# Mainboard.net
KiCad netlist of a schematic drawn in Altium Designer
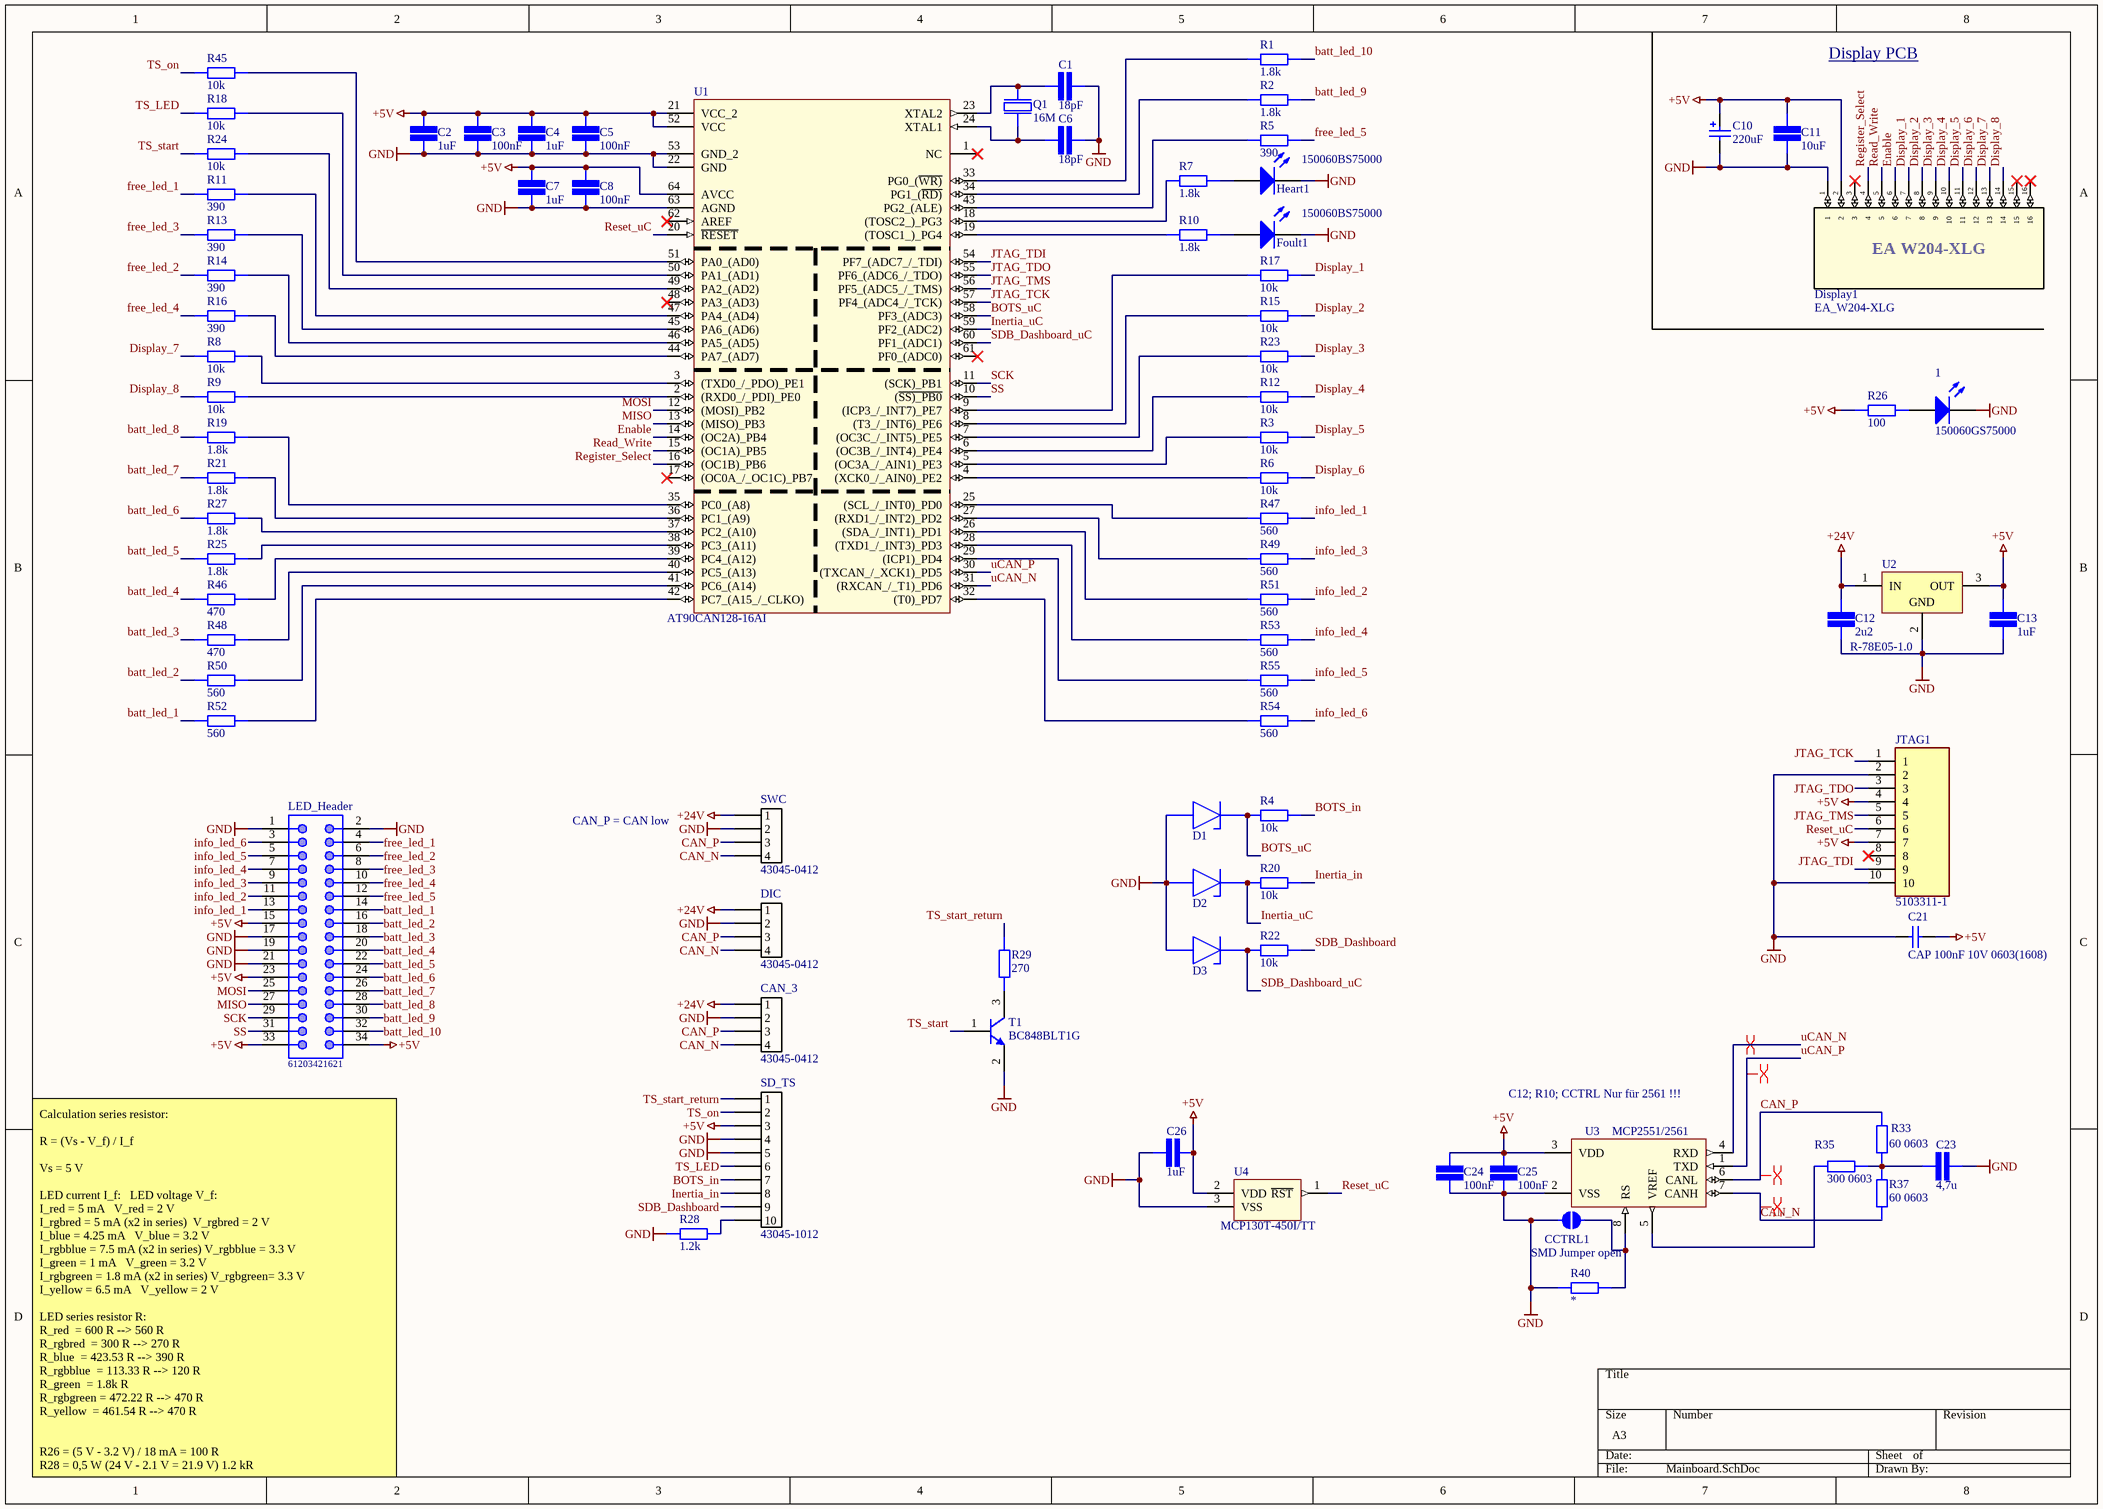
[diagram p0: Mainboard.SchDoc]

(export (version "E")
  (design (tool "Eeschema 10.0.6"))
  (components
    (comp (ref "1")
      (value "150060GS75000")
      (footprint "0603_A")
      (description "SMD mono-color Chip LED, WL-SMCW, Green")
      (fields (field (name "MANUFACTURER") "Wuerth Elektronik"))
      (libsource (lib "Altium Content Vault") (part "WE-LED_K1A2-2"))
    )
    (comp (ref "C1")
      (value "18pF")
      (footprint "CAP 0603/1608")
      (description "Capacitor with multiple Footprints")
      (fields (field (name "Comment") "SMD Capacitor"))
      (libsource (lib "Standardbauteile") (part "SMD Capacitor"))
    )
    (comp (ref "C2")
      (value "1uF")
      (footprint "CAP 0603/1608")
      (description "Capacitor with multiple Footprints")
      (fields (field (name "Comment") "SMD Capacitor"))
      (libsource (lib "") (part "SMD Capacitor_1"))
    )
    (comp (ref "C3")
      (value "100nF")
      (footprint "CAP 0603/1608")
      (description "Capacitor with multiple Footprints")
      (fields (field (name "Comment") "SMD Capacitor"))
      (libsource (lib "") (part "SMD Capacitor_1"))
    )
    (comp (ref "C4")
      (value "1uF")
      (footprint "CAP 0603/1608")
      (description "Capacitor with multiple Footprints")
      (fields (field (name "Comment") "SMD Capacitor"))
      (libsource (lib "") (part "SMD Capacitor_1"))
    )
    (comp (ref "C5")
      (value "100nF")
      (footprint "CAP 0603/1608")
      (description "Capacitor with multiple Footprints")
      (fields (field (name "Comment") "SMD Capacitor"))
      (libsource (lib "") (part "SMD Capacitor_1"))
    )
    (comp (ref "C6")
      (value "18pF")
      (footprint "CAP 0603/1608")
      (description "Capacitor with multiple Footprints")
      (fields (field (name "Comment") "SMD Capacitor"))
      (libsource (lib "Standardbauteile") (part "SMD Capacitor"))
    )
    (comp (ref "C7")
      (value "1uF")
      (footprint "CAP 0603/1608")
      (description "Capacitor with multiple Footprints")
      (fields (field (name "Comment") "SMD Capacitor"))
      (libsource (lib "") (part "SMD Capacitor_1"))
    )
    (comp (ref "C8")
      (value "100nF")
      (footprint "CAP 0603/1608")
      (description "Capacitor with multiple Footprints")
      (fields (field (name "Comment") "SMD Capacitor"))
      (libsource (lib "") (part "SMD Capacitor_1"))
    )
    (comp (ref "C10")
      (value "220uF")
      (footprint "WCAP-ASLL_6.3x7.7")
      (description "WCAP-ASLL Aluminum Electrolytic Capacitors, size Ф6.3x7.7mm, 6.3V DC, 220uF")
      (fields (field (name "PART NUMBER") "865060145006") (field (name "PUBLISHER") "Wurth Elektronik"))
      (libsource (lib "ALTIUM-WCAP-ASLL-rev17a") (part "865060145006"))
    )
    (comp (ref "C11")
      (value "10uF")
      (footprint "CAP 0603/1608")
      (description "Capacitor with multiple Footprints")
      (fields (field (name "Comment") "SMD Capacitor"))
      (libsource (lib "") (part "SMD Capacitor_2"))
    )
    (comp (ref "C12")
      (value "2u2")
      (footprint "CAP 0603/1608")
      (description "Capacitor with multiple Footprints")
      (fields (field (name "Comment") "SMD Capacitor"))
      (libsource (lib "") (part "SMD Capacitor_1"))
    )
    (comp (ref "C13")
      (value "1uF")
      (footprint "CAP 0603/1608")
      (description "Capacitor with multiple Footprints")
      (fields (field (name "Comment") "SMD Capacitor"))
      (libsource (lib "") (part "SMD Capacitor_1"))
    )
    (comp (ref "C21")
      (value "CAP 100nF 10V 0603(1608)")
      (footprint "CAPC0603(1608)100_L")
      (description "CAP 100nF 10V ±5% 0603 (1608 Metric) Thickness 1mm SMD")
      (fields (field (name "TOLERANCE") "Â±5%"))
      (libsource (lib "Altium Content Vault") (part "CAP"))
    )
    (comp (ref "C23")
      (value "4,7u")
      (footprint "CAP 0603/1608")
      (description "Capacitor with multiple Footprints")
      (fields (field (name "Comment") "SMD Capacitor"))
      (libsource (lib "") (part "SMD Capacitor_3"))
    )
    (comp (ref "C24")
      (value "100nF")
      (footprint "CAP 0603/1608")
      (description "Capacitor with multiple Footprints")
      (fields (field (name "Comment") "SMD Capacitor"))
      (libsource (lib "") (part "SMD Capacitor_1"))
    )
    (comp (ref "C25")
      (value "100nF")
      (footprint "CAP 0603/1608")
      (description "Capacitor with multiple Footprints")
      (fields (field (name "Comment") "SMD Capacitor"))
      (libsource (lib "") (part "SMD Capacitor_1"))
    )
    (comp (ref "C26")
      (value "1uF")
      (footprint "CAP 0603/1608")
      (description "Capacitor with multiple Footprints")
      (fields (field (name "Comment") "SMD Capacitor"))
      (libsource (lib "Standardbauteile") (part "SMD Capacitor"))
    )
    (comp (ref "CAN_3")
      (value "43045-0412")
      (footprint "43045-0412")
      (libsource (lib "molex_43045") (part "43045-0412"))
    )
    (comp (ref "CCTRL1")
      (value "SMD Jumper open")
      (footprint "SMD-JUMPER-OPEN")
      (libsource (lib "Standardbauteile") (part "SMD Jumper open"))
    )
    (comp (ref "D1")
      (value "MM3Z4V7T1G")
      (footprint "SOD-323-2")
      (description "onsemi MM3Z4V7T1G\r\nZ-Diode, 4,7V")
      (libsource (lib "libNico") (part "MM3Z4V7T1G"))
    )
    (comp (ref "D2")
      (value "MM3Z4V7T1G")
      (footprint "SOD-323-2")
      (description "onsemi MM3Z4V7T1G\r\nZ-Diode, 4,7V")
      (libsource (lib "libNico") (part "MM3Z4V7T1G"))
    )
    (comp (ref "D3")
      (value "MM3Z4V7T1G")
      (footprint "SOD-323-2")
      (description "onsemi MM3Z4V7T1G\r\nZ-Diode, 4,7V")
      (libsource (lib "libNico") (part "MM3Z4V7T1G"))
    )
    (comp (ref "DIC")
      (value "43045-0412")
      (footprint "43045-0412")
      (libsource (lib "molex_43045") (part "43045-0412"))
    )
    (comp (ref "Display1")
      (value "EA_W204-XLG")
      (footprint "EA_W204-XLG")
      (description "Display")
      (libsource (lib "libNico") (part "EA_W204-XLG"))
    )
    (comp (ref "Foult1")
      (value "150060BS75000")
      (footprint "0603_A")
      (description "SMD mono-color Chip LED, WL-SMCW, Blue")
      (fields (field (name "MANUFACTURER") "Wuerth Elektronik"))
      (libsource (lib "Altium Content Vault") (part "WE-LED_K1A2-2"))
    )
    (comp (ref "Heart1")
      (value "150060BS75000")
      (footprint "0603_A")
      (description "SMD mono-color Chip LED, WL-SMCW, Blue")
      (fields (field (name "MANUFACTURER") "Wuerth Elektronik"))
      (libsource (lib "Altium Content Vault") (part "WE-LED_K1A2-2"))
    )
    (comp (ref "JTAG1")
      (value "5103311-1")
      (footprint "TE_5103311-1")
      (description "AMP-LATCH Pin Header, Low Profile, 10 Pos., Right Angle PCB Mount, .100 X .100")
      (fields (field (name "MF") "TE Connectivity"))
      (libsource (lib "5103311-1") (part "5103311-1"))
    )
    (comp (ref "LED_Header")
      (value "61203421621")
      (footprint "61203421621")
      (description "WR-BHD Box Header, Male PCB side, pitch 2.54mm, THT, Straight, 34p")
      (fields (field (name "MANUFACTURER") "Wurth Elektronik"))
      (libsource (lib "Altium_WR-BHD (rev21a)") (part "61203421621"))
    )
    (comp (ref "Q1")
      (value "16M")
      (footprint "NDK NX5032GA")
      (description "16 MHz Quartz")
      (libsource (lib "Standardbauteile") (part "16 MHz Quartz"))
    )
    (comp (ref "R1")
      (value "1.8k")
      (footprint "STACKPOLE CSR0603")
      (description "Resistor with multiple footprints\r\n\r\n500R or 1kR depends on luminous intensity")
      (fields (field (name "Comment") "SMD Resistor"))
      (libsource (lib "Standardbauteile") (part "SMD Resistor"))
    )
    (comp (ref "R2")
      (value "1.8k")
      (footprint "STACKPOLE CSR0603")
      (description "Resistor with multiple footprints\r\n\r\n500R or 1kR depends on luminous intensity")
      (fields (field (name "Comment") "SMD Resistor"))
      (libsource (lib "Standardbauteile") (part "SMD Resistor"))
    )
    (comp (ref "R3")
      (value "10k")
      (footprint "STACKPOLE CSR0603")
      (description "Resistor with multiple footprints")
      (fields (field (name "Comment") "SMD Resistor"))
      (libsource (lib "Standardbauteile") (part "SMD Resistor"))
    )
    (comp (ref "R4")
      (value "10k")
      (footprint "STACKPOLE CSR0603")
      (description "Resistor with multiple footprints")
      (fields (field (name "Comment") "SMD Resistor"))
      (libsource (lib "Standardbauteile") (part "SMD Resistor"))
    )
    (comp (ref "R5")
      (value "390")
      (footprint "STACKPOLE CSR0603")
      (description "Resistor with multiple footprints\r\n\r\n500R or 1kR depends on luminous intensity")
      (fields (field (name "Comment") "SMD Resistor"))
      (libsource (lib "Standardbauteile") (part "SMD Resistor"))
    )
    (comp (ref "R6")
      (value "10k")
      (footprint "STACKPOLE CSR0603")
      (description "Resistor with multiple footprints")
      (fields (field (name "Comment") "SMD Resistor"))
      (libsource (lib "Standardbauteile") (part "SMD Resistor"))
    )
    (comp (ref "R7")
      (value "1.8k")
      (footprint "STACKPOLE CSR0603")
      (description "Resistor with multiple footprints")
      (fields (field (name "Comment") "SMD Resistor"))
      (libsource (lib "Standardbauteile") (part "SMD Resistor"))
    )
    (comp (ref "R8")
      (value "10k")
      (footprint "STACKPOLE CSR0603")
      (description "Resistor with multiple footprints")
      (fields (field (name "Comment") "SMD Resistor"))
      (libsource (lib "Standardbauteile") (part "SMD Resistor"))
    )
    (comp (ref "R9")
      (value "10k")
      (footprint "STACKPOLE CSR0603")
      (description "Resistor with multiple footprints")
      (fields (field (name "Comment") "SMD Resistor"))
      (libsource (lib "Standardbauteile") (part "SMD Resistor"))
    )
    (comp (ref "R10")
      (value "1.8k")
      (footprint "STACKPOLE CSR0603")
      (description "Resistor with multiple footprints")
      (fields (field (name "Comment") "SMD Resistor"))
      (libsource (lib "Standardbauteile") (part "SMD Resistor"))
    )
    (comp (ref "R11")
      (value "390")
      (footprint "STACKPOLE CSR0603")
      (description "Resistor with multiple footprints\r\n\r\n500R or 1kR depends on luminous intensity")
      (fields (field (name "Comment") "SMD Resistor"))
      (libsource (lib "Standardbauteile") (part "SMD Resistor"))
    )
    (comp (ref "R12")
      (value "10k")
      (footprint "STACKPOLE CSR0603")
      (description "Resistor with multiple footprints")
      (fields (field (name "Comment") "SMD Resistor"))
      (libsource (lib "Standardbauteile") (part "SMD Resistor"))
    )
    (comp (ref "R13")
      (value "390")
      (footprint "STACKPOLE CSR0603")
      (description "Resistor with multiple footprints\r\n\r\n500R or 1kR depends on luminous intensity")
      (fields (field (name "Comment") "SMD Resistor"))
      (libsource (lib "Standardbauteile") (part "SMD Resistor"))
    )
    (comp (ref "R14")
      (value "390")
      (footprint "STACKPOLE CSR0603")
      (description "Resistor with multiple footprints\r\n\r\n500R or 1kR depends on luminous intensity")
      (fields (field (name "Comment") "SMD Resistor"))
      (libsource (lib "Standardbauteile") (part "SMD Resistor"))
    )
    (comp (ref "R15")
      (value "10k")
      (footprint "STACKPOLE CSR0603")
      (description "Resistor with multiple footprints")
      (fields (field (name "Comment") "SMD Resistor"))
      (libsource (lib "Standardbauteile") (part "SMD Resistor"))
    )
    (comp (ref "R16")
      (value "390")
      (footprint "STACKPOLE CSR0603")
      (description "Resistor with multiple footprints\r\n\r\n500R or 1kR depends on luminous intensity")
      (fields (field (name "Comment") "SMD Resistor"))
      (libsource (lib "Standardbauteile") (part "SMD Resistor"))
    )
    (comp (ref "R17")
      (value "10k")
      (footprint "STACKPOLE CSR0603")
      (description "Resistor with multiple footprints")
      (fields (field (name "Comment") "SMD Resistor"))
      (libsource (lib "Standardbauteile") (part "SMD Resistor"))
    )
    (comp (ref "R18")
      (value "10k")
      (footprint "STACKPOLE CSR0603")
      (description "Resistor with multiple footprints")
      (fields (field (name "Comment") "SMD Resistor"))
      (libsource (lib "Standardbauteile") (part "SMD Resistor"))
    )
    (comp (ref "R19")
      (value "1.8k")
      (footprint "STACKPOLE CSR0603")
      (description "Resistor with multiple footprints\r\n\r\n500R or 1kR depends on luminous intensity")
      (fields (field (name "Comment") "SMD Resistor"))
      (libsource (lib "Standardbauteile") (part "SMD Resistor"))
    )
    (comp (ref "R20")
      (value "10k")
      (footprint "STACKPOLE CSR0603")
      (description "Resistor with multiple footprints")
      (fields (field (name "Comment") "SMD Resistor"))
      (libsource (lib "Standardbauteile") (part "SMD Resistor"))
    )
    (comp (ref "R21")
      (value "1.8k")
      (footprint "STACKPOLE CSR0603")
      (description "Resistor with multiple footprints\r\n\r\n500R or 1kR depends on luminous intensity")
      (fields (field (name "Comment") "SMD Resistor"))
      (libsource (lib "Standardbauteile") (part "SMD Resistor"))
    )
    (comp (ref "R22")
      (value "10k")
      (footprint "STACKPOLE CSR0603")
      (description "Resistor with multiple footprints")
      (fields (field (name "Comment") "SMD Resistor"))
      (libsource (lib "Standardbauteile") (part "SMD Resistor"))
    )
    (comp (ref "R23")
      (value "10k")
      (footprint "STACKPOLE CSR0603")
      (description "Resistor with multiple footprints")
      (fields (field (name "Comment") "SMD Resistor"))
      (libsource (lib "Standardbauteile") (part "SMD Resistor"))
    )
    (comp (ref "R24")
      (value "10k")
      (footprint "STACKPOLE CSR0603")
      (description "Resistor with multiple footprints")
      (fields (field (name "Comment") "SMD Resistor"))
      (libsource (lib "Standardbauteile") (part "SMD Resistor"))
    )
    (comp (ref "R25")
      (value "1.8k")
      (footprint "STACKPOLE CSR0603")
      (description "Resistor with multiple footprints\r\n\r\n500R or 1kR depends on luminous intensity")
      (fields (field (name "Comment") "SMD Resistor"))
      (libsource (lib "Standardbauteile") (part "SMD Resistor"))
    )
    (comp (ref "R26")
      (value "100")
      (footprint "STACKPOLE CSR0603")
      (description "Resistor with multiple footprints")
      (fields (field (name "Comment") "SMD Resistor"))
      (libsource (lib "Standardbauteile") (part "SMD Resistor"))
    )
    (comp (ref "R27")
      (value "1.8k")
      (footprint "STACKPOLE CSR0603")
      (description "Resistor with multiple footprints\r\n\r\n500R or 1kR depends on luminous intensity")
      (fields (field (name "Comment") "SMD Resistor"))
      (libsource (lib "Standardbauteile") (part "SMD Resistor"))
    )
    (comp (ref "R28")
      (value "1.2k")
      (footprint "STACKPOLE CSR0805")
      (description "Resistor with multiple footprints")
      (fields (field (name "Comment") "SMD Resistor"))
      (libsource (lib "Standardbauteile") (part "SMD Resistor"))
    )
    (comp (ref "R29")
      (value "270")
      (footprint "STACKPOLE CSR0603")
      (description "Resistor with multiple footprints")
      (fields (field (name "Comment") "SMD Resistor"))
      (libsource (lib "Standardbauteile") (part "SMD Resistor"))
    )
    (comp (ref "R33")
      (value "60 0603")
      (footprint "STACKPOLE CSR0603")
      (description "Resistor with multiple footprints")
      (fields (field (name "Comment") "SMD Resistor"))
      (libsource (lib "Standardbauteile") (part "SMD Resistor"))
    )
    (comp (ref "R35")
      (value "300 0603")
      (footprint "STACKPOLE CSR0603")
      (description "Resistor with multiple footprints")
      (fields (field (name "Comment") "SMD Resistor"))
      (libsource (lib "Standardbauteile") (part "SMD Resistor"))
    )
    (comp (ref "R37")
      (value "60 0603")
      (footprint "STACKPOLE CSR0603")
      (description "Resistor with multiple footprints")
      (fields (field (name "Comment") "SMD Resistor"))
      (libsource (lib "Standardbauteile") (part "SMD Resistor"))
    )
    (comp (ref "R40")
      (value "SMD Resistor")
      (footprint "STACKPOLE CSR0603")
      (description "Resistor with multiple footprints")
      (fields (field (name "ALTIUM_VALUE") "*"))
      (libsource (lib "Standardbauteile") (part "SMD Resistor"))
    )
    (comp (ref "R45")
      (value "10k")
      (footprint "STACKPOLE CSR0603")
      (description "Resistor with multiple footprints")
      (fields (field (name "Comment") "SMD Resistor"))
      (libsource (lib "Standardbauteile") (part "SMD Resistor"))
    )
    (comp (ref "R46")
      (value "470")
      (footprint "STACKPOLE CSR0603")
      (description "Resistor with multiple footprints\r\n\r\n500R or 1kR depends on luminous intensity")
      (fields (field (name "Comment") "SMD Resistor"))
      (libsource (lib "Standardbauteile") (part "SMD Resistor"))
    )
    (comp (ref "R47")
      (value "560")
      (footprint "STACKPOLE CSR0603")
      (description "Resistor with multiple footprints")
      (fields (field (name "Comment") "SMD Resistor"))
      (libsource (lib "Standardbauteile") (part "SMD Resistor"))
    )
    (comp (ref "R48")
      (value "470")
      (footprint "STACKPOLE CSR0603")
      (description "Resistor with multiple footprints\r\n\r\n500R or 1kR depends on luminous intensity")
      (fields (field (name "Comment") "SMD Resistor"))
      (libsource (lib "Standardbauteile") (part "SMD Resistor"))
    )
    (comp (ref "R49")
      (value "560")
      (footprint "STACKPOLE CSR0603")
      (description "Resistor with multiple footprints")
      (fields (field (name "Comment") "SMD Resistor"))
      (libsource (lib "Standardbauteile") (part "SMD Resistor"))
    )
    (comp (ref "R50")
      (value "560")
      (footprint "STACKPOLE CSR0603")
      (description "Resistor with multiple footprints\r\n\r\n500R or 1kR depends on luminous intensity")
      (fields (field (name "Comment") "SMD Resistor"))
      (libsource (lib "Standardbauteile") (part "SMD Resistor"))
    )
    (comp (ref "R51")
      (value "560")
      (footprint "STACKPOLE CSR0603")
      (description "Resistor with multiple footprints")
      (fields (field (name "Comment") "SMD Resistor"))
      (libsource (lib "Standardbauteile") (part "SMD Resistor"))
    )
    (comp (ref "R52")
      (value "560")
      (footprint "STACKPOLE CSR0603")
      (description "Resistor with multiple footprints\r\n\r\n500R or 1kR depends on luminous intensity")
      (fields (field (name "Comment") "SMD Resistor"))
      (libsource (lib "Standardbauteile") (part "SMD Resistor"))
    )
    (comp (ref "R53")
      (value "560")
      (footprint "STACKPOLE CSR0603")
      (description "Resistor with multiple footprints")
      (fields (field (name "Comment") "SMD Resistor"))
      (libsource (lib "Standardbauteile") (part "SMD Resistor"))
    )
    (comp (ref "R54")
      (value "560")
      (footprint "STACKPOLE CSR0603")
      (description "Resistor with multiple footprints")
      (fields (field (name "Comment") "SMD Resistor"))
      (libsource (lib "Standardbauteile") (part "SMD Resistor"))
    )
    (comp (ref "R55")
      (value "560")
      (footprint "STACKPOLE CSR0603")
      (description "Resistor with multiple footprints")
      (fields (field (name "Comment") "SMD Resistor"))
      (libsource (lib "Standardbauteile") (part "SMD Resistor"))
    )
    (comp (ref "SD_TS")
      (value "43045-1012")
      (footprint "43045-1012")
      (libsource (lib "molex_43045") (part "43045-1012"))
    )
    (comp (ref "SWC")
      (value "43045-0412")
      (footprint "43045-0412")
      (libsource (lib "molex_43045") (part "43045-0412"))
    )
    (comp (ref "T1")
      (value "BC848BLT1G")
      (footprint "ONSC-SOT-23-3-318-08_V")
      (description "General Purpose Transistor, NPN Silicon, 3-Pin SOT-23, Pb-Free, Tape and Reel")
      (fields (field (name "MANUFACTURER") "On Semiconductor"))
      (libsource (lib "BSPDLukas") (part "CMP-1048-00679-1"))
    )
    (comp (ref "U1")
      (value "AT90CAN128-16AI")
      (footprint "*QFP80P1600X1600X120-64N")
      (description "Ic Mcu 8bit 128kb Flash 64tqfp")
      (fields (field (name "MF") "Microchip"))
      (libsource (lib "Eric") (part "AT90CAN128-16AI"))
    )
    (comp (ref "U2")
      (value "R-78E05-1.0")
      (footprint "SIP3_RECOM")
      (description "Nonisolated 5V Switchmode converter")
      (libsource (lib "Standardbauteile") (part "R-78E05-1.0"))
    )
    (comp (ref "U3")
      (value "MCP2551/2561")
      (footprint "*SOIC127P600X175-8N")
      (description "MCP2551 Series 5.5 V 1 Mb/s Surface Mount High-Speed CAN Transceiver - SOIC-8")
      (fields (field (name "MP") "MCP2551-I/SN") (field (name "MF") "Microchip"))
      (libsource (lib "Eric") (part "MCP2551-I/SN"))
    )
    (comp (ref "U4")
      (value "MCP130T-450I/TT")
      (footprint "*SOT95P237X112-3N")
      (description "System Supervisors - Power Supply Monitors with Reset Generators Open Drain Low")
      (fields (field (name "MF") "Microchip") (field (name "MP") "MCP120T-450I/TT"))
      (libsource (lib "Eric") (part "MCP130T-450I/TT"))
    )
  )
  (nets
    (net (code "1") (name "+5V") (class "Default")
      (node (ref "C10") (pin "1") (pinfunction "P_1") (pintype "passive"))
      (node (ref "C11") (pin "1") (pinfunction "1_1") (pintype "passive"))
      (node (ref "C13") (pin "2") (pinfunction "2_2") (pintype "passive"))
      (node (ref "C2") (pin "2") (pinfunction "2_2") (pintype "passive"))
      (node (ref "C21") (pin "1") (pinfunction "1_1") (pintype "passive"))
      (node (ref "C24") (pin "2") (pinfunction "2_2") (pintype "passive"))
      (node (ref "C25") (pin "2") (pinfunction "2_2") (pintype "passive"))
      (node (ref "C26") (pin "1") (pinfunction "1_1") (pintype "passive"))
      (node (ref "C3") (pin "2") (pinfunction "2_2") (pintype "passive"))
      (node (ref "C4") (pin "2") (pinfunction "2_2") (pintype "passive"))
      (node (ref "C5") (pin "2") (pinfunction "2_2") (pintype "passive"))
      (node (ref "C7") (pin "2") (pinfunction "2_2") (pintype "passive"))
      (node (ref "C8") (pin "2") (pinfunction "2_2") (pintype "passive"))
      (node (ref "Display1") (pin "2") (pinfunction "2_2") (pintype "bidirectional"))
      (node (ref "JTAG1") (pin "4") (pinfunction "4_4") (pintype "passive"))
      (node (ref "JTAG1") (pin "7") (pinfunction "7_7") (pintype "passive"))
      (node (ref "LED_Header") (pin "15") (pinfunction "15_15") (pintype "passive"))
      (node (ref "LED_Header") (pin "23") (pinfunction "23_23") (pintype "passive"))
      (node (ref "LED_Header") (pin "33") (pinfunction "33_33") (pintype "passive"))
      (node (ref "LED_Header") (pin "34") (pinfunction "34_34") (pintype "passive"))
      (node (ref "R26") (pin "1") (pinfunction "1_1") (pintype "passive"))
      (node (ref "SD_TS") (pin "3") (pinfunction "3_3") (pintype "passive"))
      (node (ref "U1") (pin "21") (pinfunction "VCC_2_21") (pintype "power_in"))
      (node (ref "U1") (pin "52") (pinfunction "VCC_52") (pintype "power_in"))
      (node (ref "U1") (pin "64") (pinfunction "AVCC_64") (pintype "power_in"))
      (node (ref "U2") (pin "3") (pinfunction "OUT_3") (pintype "power_in"))
      (node (ref "U3") (pin "3") (pinfunction "VDD_3") (pintype "power_in"))
      (node (ref "U4") (pin "2") (pinfunction "VDD_2") (pintype "power_in"))
    )
    (net (code "2") (name "+24V") (class "Default")
      (node (ref "C12") (pin "2") (pinfunction "2_2") (pintype "passive"))
      (node (ref "CAN_3") (pin "1") (pinfunction "1_1") (pintype "passive"))
      (node (ref "DIC") (pin "1") (pinfunction "1_1") (pintype "passive"))
      (node (ref "SWC") (pin "1") (pinfunction "1_1") (pintype "passive"))
      (node (ref "U2") (pin "1") (pinfunction "IN_1") (pintype "power_in"))
    )
    (net (code "3") (name "/BOTS_in") (class "Default")
      (node (ref "R4") (pin "1") (pinfunction "1_1") (pintype "passive"))
      (node (ref "SD_TS") (pin "7") (pinfunction "7_7") (pintype "passive"))
    )
    (net (code "4") (name "/BOTS_uC") (class "Default")
      (node (ref "D1") (pin "1C") (pinfunction "C_1C") (pintype "passive"))
      (node (ref "R4") (pin "2") (pinfunction "2_2") (pintype "passive"))
      (node (ref "U1") (pin "58") (pinfunction "PF3_(ADC3)_58") (pintype "bidirectional"))
    )
    (net (code "5") (name "/CAN_N") (class "Default")
      (node (ref "CAN_3") (pin "4") (pinfunction "4_4") (pintype "passive"))
      (node (ref "DIC") (pin "4") (pinfunction "4_4") (pintype "passive"))
      (node (ref "R37") (pin "2") (pinfunction "2_2") (pintype "passive"))
      (node (ref "SWC") (pin "4") (pinfunction "4_4") (pintype "passive"))
      (node (ref "U3") (pin "7") (pinfunction "CANH_7") (pintype "bidirectional"))
    )
    (net (code "6") (name "/CAN_P") (class "Default")
      (node (ref "CAN_3") (pin "3") (pinfunction "3_3") (pintype "passive"))
      (node (ref "DIC") (pin "3") (pinfunction "3_3") (pintype "passive"))
      (node (ref "R33") (pin "1") (pinfunction "1_1") (pintype "passive"))
      (node (ref "SWC") (pin "3") (pinfunction "3_3") (pintype "passive"))
      (node (ref "U3") (pin "6") (pinfunction "CANL_6") (pintype "bidirectional"))
    )
    (net (code "7") (name "/Display_1") (class "Default")
      (node (ref "Display1") (pin "7") (pinfunction "7_7") (pintype "bidirectional"))
      (node (ref "R17") (pin "1") (pinfunction "1_1") (pintype "passive"))
    )
    (net (code "8") (name "/Display_2") (class "Default")
      (node (ref "Display1") (pin "8") (pinfunction "8_8") (pintype "bidirectional"))
      (node (ref "R15") (pin "1") (pinfunction "1_1") (pintype "passive"))
    )
    (net (code "9") (name "/Display_3") (class "Default")
      (node (ref "Display1") (pin "9") (pinfunction "9_9") (pintype "bidirectional"))
      (node (ref "R23") (pin "2") (pinfunction "2_2") (pintype "passive"))
    )
    (net (code "10") (name "/Display_4") (class "Default")
      (node (ref "Display1") (pin "10") (pinfunction "10_10") (pintype "bidirectional"))
      (node (ref "R12") (pin "1") (pinfunction "1_1") (pintype "passive"))
    )
    (net (code "11") (name "/Display_5") (class "Default")
      (node (ref "Display1") (pin "11") (pinfunction "11_11") (pintype "bidirectional"))
      (node (ref "R3") (pin "2") (pinfunction "2_2") (pintype "passive"))
    )
    (net (code "12") (name "/Display_6") (class "Default")
      (node (ref "Display1") (pin "12") (pinfunction "12_12") (pintype "bidirectional"))
      (node (ref "R6") (pin "2") (pinfunction "2_2") (pintype "passive"))
    )
    (net (code "13") (name "/Display_7") (class "Default")
      (node (ref "Display1") (pin "13") (pinfunction "13_13") (pintype "bidirectional"))
      (node (ref "R8") (pin "1") (pinfunction "1_1") (pintype "passive"))
    )
    (net (code "14") (name "/Display_8") (class "Default")
      (node (ref "Display1") (pin "14") (pinfunction "14_14") (pintype "bidirectional"))
      (node (ref "R9") (pin "1") (pinfunction "1_1") (pintype "passive"))
    )
    (net (code "15") (name "/Enable") (class "Default")
      (node (ref "Display1") (pin "6") (pinfunction "6_6") (pintype "bidirectional"))
      (node (ref "U1") (pin "14") (pinfunction "(OC2A)_PB4_14") (pintype "bidirectional"))
    )
    (net (code "16") (name "/Inertia_in") (class "Default")
      (node (ref "R20") (pin "1") (pinfunction "1_1") (pintype "passive"))
      (node (ref "SD_TS") (pin "8") (pinfunction "8_8") (pintype "passive"))
    )
    (net (code "17") (name "/Inertia_uC") (class "Default")
      (node (ref "D2") (pin "1C") (pinfunction "C_1C") (pintype "passive"))
      (node (ref "R20") (pin "2") (pinfunction "2_2") (pintype "passive"))
      (node (ref "U1") (pin "59") (pinfunction "PF2_(ADC2)_59") (pintype "bidirectional"))
    )
    (net (code "18") (name "/JTAG_TCK") (class "Default")
      (node (ref "JTAG1") (pin "1") (pinfunction "1_1") (pintype "passive"))
      (node (ref "U1") (pin "57") (pinfunction "PF4_(ADC4_/_TCK)_57") (pintype "bidirectional"))
    )
    (net (code "19") (name "/JTAG_TDI") (class "Default")
      (node (ref "JTAG1") (pin "9") (pinfunction "9_9") (pintype "passive"))
      (node (ref "U1") (pin "54") (pinfunction "PF7_(ADC7_/_TDI)_54") (pintype "bidirectional"))
    )
    (net (code "20") (name "/JTAG_TDO") (class "Default")
      (node (ref "JTAG1") (pin "3") (pinfunction "3_3") (pintype "passive"))
      (node (ref "U1") (pin "55") (pinfunction "PF6_(ADC6_/_TDO)_55") (pintype "bidirectional"))
    )
    (net (code "21") (name "/JTAG_TMS") (class "Default")
      (node (ref "JTAG1") (pin "5") (pinfunction "5_5") (pintype "passive"))
      (node (ref "U1") (pin "56") (pinfunction "PF5_(ADC5_/_TMS)_56") (pintype "bidirectional"))
    )
    (net (code "22") (name "/MISO") (class "Default")
      (node (ref "LED_Header") (pin "27") (pinfunction "27_27") (pintype "passive"))
      (node (ref "U1") (pin "13") (pinfunction "(MISO)_PB3_13") (pintype "bidirectional"))
    )
    (net (code "23") (name "/MOSI") (class "Default")
      (node (ref "LED_Header") (pin "25") (pinfunction "25_25") (pintype "passive"))
      (node (ref "U1") (pin "12") (pinfunction "(MOSI)_PB2_12") (pintype "bidirectional"))
    )
    (net (code "24") (name "/Read_Write") (class "Default")
      (node (ref "Display1") (pin "5") (pinfunction "5_5") (pintype "bidirectional"))
      (node (ref "U1") (pin "15") (pinfunction "(OC1A)_PB5_15") (pintype "bidirectional"))
    )
    (net (code "25") (name "/Register_Select") (class "Default")
      (node (ref "Display1") (pin "4") (pinfunction "4_4") (pintype "bidirectional"))
      (node (ref "U1") (pin "16") (pinfunction "(OC1B)_PB6_16") (pintype "bidirectional"))
    )
    (net (code "26") (name "/Reset_uC") (class "Default")
      (node (ref "JTAG1") (pin "6") (pinfunction "6_6") (pintype "passive"))
      (node (ref "U1") (pin "20") (pinfunction "~{RESET}_20") (pintype "input"))
      (node (ref "U4") (pin "1") (pinfunction "~{RST}_1") (pintype "output"))
    )
    (net (code "27") (name "/SCK") (class "Default")
      (node (ref "LED_Header") (pin "29") (pinfunction "29_29") (pintype "passive"))
      (node (ref "U1") (pin "11") (pinfunction "(SCK)_PB1_11") (pintype "bidirectional"))
    )
    (net (code "28") (name "/SDB_Dashboard") (class "Default")
      (node (ref "R22") (pin "1") (pinfunction "1_1") (pintype "passive"))
      (node (ref "SD_TS") (pin "9") (pinfunction "9_9") (pintype "passive"))
    )
    (net (code "29") (name "/SDB_Dashboard_uC") (class "Default")
      (node (ref "D3") (pin "1C") (pinfunction "C_1C") (pintype "passive"))
      (node (ref "R22") (pin "2") (pinfunction "2_2") (pintype "passive"))
      (node (ref "U1") (pin "60") (pinfunction "PF1_(ADC1)_60") (pintype "bidirectional"))
    )
    (net (code "30") (name "/SS") (class "Default")
      (node (ref "LED_Header") (pin "31") (pinfunction "31_31") (pintype "passive"))
      (node (ref "U1") (pin "10") (pinfunction "(~{SS)_PB0}_10") (pintype "bidirectional"))
    )
    (net (code "31") (name "/TS_LED") (class "Default")
      (node (ref "R18") (pin "1") (pinfunction "1_1") (pintype "passive"))
      (node (ref "SD_TS") (pin "6") (pinfunction "6_6") (pintype "passive"))
    )
    (net (code "32") (name "/TS_on") (class "Default")
      (node (ref "R45") (pin "2") (pinfunction "2_2") (pintype "passive"))
      (node (ref "SD_TS") (pin "2") (pinfunction "2_2") (pintype "passive"))
    )
    (net (code "33") (name "/TS_start") (class "Default")
      (node (ref "R24") (pin "2") (pinfunction "2_2") (pintype "passive"))
      (node (ref "T1") (pin "1") (pinfunction "B_1") (pintype "passive"))
    )
    (net (code "34") (name "/TS_start_return") (class "Default")
      (node (ref "R29") (pin "1") (pinfunction "1_1") (pintype "passive"))
      (node (ref "SD_TS") (pin "1") (pinfunction "1_1") (pintype "passive"))
    )
    (net (code "35") (name "/batt_led_1") (class "Default")
      (node (ref "LED_Header") (pin "14") (pinfunction "14_14") (pintype "passive"))
      (node (ref "R52") (pin "1") (pinfunction "1_1") (pintype "passive"))
    )
    (net (code "36") (name "/batt_led_2") (class "Default")
      (node (ref "LED_Header") (pin "16") (pinfunction "16_16") (pintype "passive"))
      (node (ref "R50") (pin "1") (pinfunction "1_1") (pintype "passive"))
    )
    (net (code "37") (name "/batt_led_3") (class "Default")
      (node (ref "LED_Header") (pin "18") (pinfunction "18_18") (pintype "passive"))
      (node (ref "R48") (pin "1") (pinfunction "1_1") (pintype "passive"))
    )
    (net (code "38") (name "/batt_led_4") (class "Default")
      (node (ref "LED_Header") (pin "20") (pinfunction "20_20") (pintype "passive"))
      (node (ref "R46") (pin "1") (pinfunction "1_1") (pintype "passive"))
    )
    (net (code "39") (name "/batt_led_5") (class "Default")
      (node (ref "LED_Header") (pin "22") (pinfunction "22_22") (pintype "passive"))
      (node (ref "R25") (pin "2") (pinfunction "2_2") (pintype "passive"))
    )
    (net (code "40") (name "/batt_led_6") (class "Default")
      (node (ref "LED_Header") (pin "24") (pinfunction "24_24") (pintype "passive"))
      (node (ref "R27") (pin "2") (pinfunction "2_2") (pintype "passive"))
    )
    (net (code "41") (name "/batt_led_7") (class "Default")
      (node (ref "LED_Header") (pin "26") (pinfunction "26_26") (pintype "passive"))
      (node (ref "R21") (pin "1") (pinfunction "1_1") (pintype "passive"))
    )
    (net (code "42") (name "/batt_led_8") (class "Default")
      (node (ref "LED_Header") (pin "28") (pinfunction "28_28") (pintype "passive"))
      (node (ref "R19") (pin "1") (pinfunction "1_1") (pintype "passive"))
    )
    (net (code "43") (name "/batt_led_9") (class "Default")
      (node (ref "LED_Header") (pin "30") (pinfunction "30_30") (pintype "passive"))
      (node (ref "R2") (pin "1") (pinfunction "1_1") (pintype "passive"))
    )
    (net (code "44") (name "/batt_led_10") (class "Default")
      (node (ref "LED_Header") (pin "32") (pinfunction "32_32") (pintype "passive"))
      (node (ref "R1") (pin "1") (pinfunction "1_1") (pintype "passive"))
    )
    (net (code "45") (name "/free_led_1") (class "Default")
      (node (ref "LED_Header") (pin "4") (pinfunction "4_4") (pintype "passive"))
      (node (ref "R11") (pin "2") (pinfunction "2_2") (pintype "passive"))
    )
    (net (code "46") (name "/free_led_2") (class "Default")
      (node (ref "LED_Header") (pin "6") (pinfunction "6_6") (pintype "passive"))
      (node (ref "R14") (pin "2") (pinfunction "2_2") (pintype "passive"))
    )
    (net (code "47") (name "/free_led_3") (class "Default")
      (node (ref "LED_Header") (pin "8") (pinfunction "8_8") (pintype "passive"))
      (node (ref "R13") (pin "2") (pinfunction "2_2") (pintype "passive"))
    )
    (net (code "48") (name "/free_led_4") (class "Default")
      (node (ref "LED_Header") (pin "10") (pinfunction "10_10") (pintype "passive"))
      (node (ref "R16") (pin "2") (pinfunction "2_2") (pintype "passive"))
    )
    (net (code "49") (name "/free_led_5") (class "Default")
      (node (ref "LED_Header") (pin "12") (pinfunction "12_12") (pintype "passive"))
      (node (ref "R5") (pin "1") (pinfunction "1_1") (pintype "passive"))
    )
    (net (code "50") (name "/info_led_1") (class "Default")
      (node (ref "LED_Header") (pin "13") (pinfunction "13_13") (pintype "passive"))
      (node (ref "R47") (pin "2") (pinfunction "2_2") (pintype "passive"))
    )
    (net (code "51") (name "/info_led_2") (class "Default")
      (node (ref "LED_Header") (pin "11") (pinfunction "11_11") (pintype "passive"))
      (node (ref "R51") (pin "2") (pinfunction "2_2") (pintype "passive"))
    )
    (net (code "52") (name "/info_led_3") (class "Default")
      (node (ref "LED_Header") (pin "9") (pinfunction "9_9") (pintype "passive"))
      (node (ref "R49") (pin "1") (pinfunction "1_1") (pintype "passive"))
    )
    (net (code "53") (name "/info_led_4") (class "Default")
      (node (ref "LED_Header") (pin "7") (pinfunction "7_7") (pintype "passive"))
      (node (ref "R53") (pin "2") (pinfunction "2_2") (pintype "passive"))
    )
    (net (code "54") (name "/info_led_5") (class "Default")
      (node (ref "LED_Header") (pin "5") (pinfunction "5_5") (pintype "passive"))
      (node (ref "R55") (pin "2") (pinfunction "2_2") (pintype "passive"))
    )
    (net (code "55") (name "/info_led_6") (class "Default")
      (node (ref "LED_Header") (pin "3") (pinfunction "3_3") (pintype "passive"))
      (node (ref "R54") (pin "2") (pinfunction "2_2") (pintype "passive"))
    )
    (net (code "56") (name "/uCAN_N") (class "Default")
      (node (ref "U1") (pin "31") (pinfunction "(RXCAN_/_T1)_PD6_31") (pintype "bidirectional"))
      (node (ref "U3") (pin "4") (pinfunction "RXD_4") (pintype "output"))
    )
    (net (code "57") (name "/uCAN_P") (class "Default")
      (node (ref "U1") (pin "30") (pinfunction "(TXCAN_/_XCK1)_PD5_30") (pintype "bidirectional"))
      (node (ref "U3") (pin "1") (pinfunction "TXD_1") (pintype "input"))
    )
    (net (code "58") (name "GND") (class "Default")
      (node (ref "1") (pin "1") (pinfunction "K_1") (pintype "passive"))
      (node (ref "C1") (pin "1") (pinfunction "1_1") (pintype "passive"))
      (node (ref "C10") (pin "2") (pinfunction "N_2") (pintype "passive"))
      (node (ref "C11") (pin "2") (pinfunction "2_2") (pintype "passive"))
      (node (ref "C12") (pin "1") (pinfunction "1_1") (pintype "passive"))
      (node (ref "C13") (pin "1") (pinfunction "1_1") (pintype "passive"))
      (node (ref "C2") (pin "1") (pinfunction "1_1") (pintype "passive"))
      (node (ref "C21") (pin "2") (pinfunction "2_2") (pintype "passive"))
      (node (ref "C23") (pin "2") (pinfunction "2_2") (pintype "passive"))
      (node (ref "C24") (pin "1") (pinfunction "1_1") (pintype "passive"))
      (node (ref "C25") (pin "1") (pinfunction "1_1") (pintype "passive"))
      (node (ref "C26") (pin "2") (pinfunction "2_2") (pintype "passive"))
      (node (ref "C3") (pin "1") (pinfunction "1_1") (pintype "passive"))
      (node (ref "C4") (pin "1") (pinfunction "1_1") (pintype "passive"))
      (node (ref "C5") (pin "1") (pinfunction "1_1") (pintype "passive"))
      (node (ref "C6") (pin "1") (pinfunction "1_1") (pintype "passive"))
      (node (ref "C7") (pin "1") (pinfunction "1_1") (pintype "passive"))
      (node (ref "C8") (pin "1") (pinfunction "1_1") (pintype "passive"))
      (node (ref "CAN_3") (pin "2") (pinfunction "2_2") (pintype "passive"))
      (node (ref "CCTRL1") (pin "1") (pinfunction "1_1") (pintype "passive"))
      (node (ref "D1") (pin "2A") (pinfunction "A_2A") (pintype "passive"))
      (node (ref "D2") (pin "2A") (pinfunction "A_2A") (pintype "passive"))
      (node (ref "D3") (pin "2A") (pinfunction "A_2A") (pintype "passive"))
      (node (ref "DIC") (pin "2") (pinfunction "2_2") (pintype "passive"))
      (node (ref "Display1") (pin "1") (pinfunction "1_1") (pintype "bidirectional"))
      (node (ref "Foult1") (pin "1") (pinfunction "K_1") (pintype "passive"))
      (node (ref "Heart1") (pin "1") (pinfunction "K_1") (pintype "passive"))
      (node (ref "JTAG1") (pin "10") (pinfunction "10_10") (pintype "passive"))
      (node (ref "JTAG1") (pin "2") (pinfunction "2_2") (pintype "passive"))
      (node (ref "LED_Header") (pin "1") (pinfunction "1_1") (pintype "passive"))
      (node (ref "LED_Header") (pin "17") (pinfunction "17_17") (pintype "passive"))
      (node (ref "LED_Header") (pin "19") (pinfunction "19_19") (pintype "passive"))
      (node (ref "LED_Header") (pin "2") (pinfunction "2_2") (pintype "passive"))
      (node (ref "LED_Header") (pin "21") (pinfunction "21_21") (pintype "passive"))
      (node (ref "R28") (pin "2") (pinfunction "2_2") (pintype "passive"))
      (node (ref "R40") (pin "1") (pinfunction "1_1") (pintype "passive"))
      (node (ref "SD_TS") (pin "4") (pinfunction "4_4") (pintype "passive"))
      (node (ref "SD_TS") (pin "5") (pinfunction "5_5") (pintype "passive"))
      (node (ref "SWC") (pin "2") (pinfunction "2_2") (pintype "passive"))
      (node (ref "T1") (pin "2") (pinfunction "E_2") (pintype "passive"))
      (node (ref "U1") (pin "22") (pinfunction "GND_22") (pintype "passive"))
      (node (ref "U1") (pin "53") (pinfunction "GND_2_53") (pintype "passive"))
      (node (ref "U1") (pin "63") (pinfunction "AGND_63") (pintype "passive"))
      (node (ref "U2") (pin "2") (pinfunction "GND_2") (pintype "power_in"))
      (node (ref "U3") (pin "2") (pinfunction "VSS_2") (pintype "passive"))
      (node (ref "U4") (pin "3") (pinfunction "VSS_3") (pintype "power_in"))
    )
    (net (code "59") (name "Net-(1-A)") (class "Default")
      (node (ref "1") (pin "2") (pinfunction "A_2") (pintype "passive"))
      (node (ref "R26") (pin "2") (pinfunction "2_2") (pintype "passive"))
    )
    (net (code "60") (name "Net-(C23-Pad1)") (class "Default")
      (node (ref "C23") (pin "1") (pinfunction "1_1") (pintype "passive"))
      (node (ref "R33") (pin "2") (pinfunction "2_2") (pintype "passive"))
      (node (ref "R35") (pin "2") (pinfunction "2_2") (pintype "passive"))
      (node (ref "R37") (pin "1") (pinfunction "1_1") (pintype "passive"))
    )
    (net (code "61") (name "Net-(Foult1-A)") (class "Default")
      (node (ref "Foult1") (pin "2") (pinfunction "A_2") (pintype "passive"))
      (node (ref "R10") (pin "2") (pinfunction "2_2") (pintype "passive"))
    )
    (net (code "62") (name "Net-(Heart1-A)") (class "Default")
      (node (ref "Heart1") (pin "2") (pinfunction "A_2") (pintype "passive"))
      (node (ref "R7") (pin "2") (pinfunction "2_2") (pintype "passive"))
    )
    (net (code "63") (name "Net-(R28-Pad1)") (class "Default")
      (node (ref "R28") (pin "1") (pinfunction "1_1") (pintype "passive"))
      (node (ref "SD_TS") (pin "10") (pinfunction "10_10") (pintype "passive"))
    )
    (net (code "64") (name "Net-(T1-C)") (class "Default")
      (node (ref "R29") (pin "2") (pinfunction "2_2") (pintype "passive"))
      (node (ref "T1") (pin "3") (pinfunction "C_3") (pintype "passive"))
    )
    (net (code "65") (name "Net-(U1-(ICP1)_PD4)") (class "Default")
      (node (ref "R55") (pin "1") (pinfunction "1_1") (pintype "passive"))
      (node (ref "U1") (pin "29") (pinfunction "(ICP1)_PD4_29") (pintype "bidirectional"))
    )
    (net (code "66") (name "Net-(U1-(ICP3_{slash}_INT7)_PE7)") (class "Default")
      (node (ref "R17") (pin "2") (pinfunction "2_2") (pintype "passive"))
      (node (ref "U1") (pin "9") (pinfunction "(ICP3_/_INT7)_PE7_9") (pintype "bidirectional"))
    )
    (net (code "67") (name "Net-(U1-(OC3A_{slash}_AIN1)_PE3)") (class "Default")
      (node (ref "R3") (pin "1") (pinfunction "1_1") (pintype "passive"))
      (node (ref "U1") (pin "5") (pinfunction "(OC3A_/_AIN1)_PE3_5") (pintype "bidirectional"))
    )
    (net (code "68") (name "Net-(U1-(OC3B_{slash}_INT4)_PE4)") (class "Default")
      (node (ref "R12") (pin "2") (pinfunction "2_2") (pintype "passive"))
      (node (ref "U1") (pin "6") (pinfunction "(OC3B_/_INT4)_PE4_6") (pintype "bidirectional"))
    )
    (net (code "69") (name "Net-(U1-(OC3C_{slash}_INT5)_PE5)") (class "Default")
      (node (ref "R23") (pin "1") (pinfunction "1_1") (pintype "passive"))
      (node (ref "U1") (pin "7") (pinfunction "(OC3C_/_INT5)_PE5_7") (pintype "bidirectional"))
    )
    (net (code "70") (name "Net-(U1-(RXD0_{slash}_PDI)_PE0)") (class "Default")
      (node (ref "R9") (pin "2") (pinfunction "2_2") (pintype "passive"))
      (node (ref "U1") (pin "2") (pinfunction "(RXD0_/_PDI)_PE0_2") (pintype "bidirectional"))
    )
    (net (code "71") (name "Net-(U1-(RXD1_{slash}_INT2)_PD2)") (class "Default")
      (node (ref "R49") (pin "2") (pinfunction "2_2") (pintype "passive"))
      (node (ref "U1") (pin "27") (pinfunction "(RXD1_/_INT2)_PD2_27") (pintype "bidirectional"))
    )
    (net (code "72") (name "Net-(U1-(SCL_{slash}_INT0)_PD0)") (class "Default")
      (node (ref "R47") (pin "1") (pinfunction "1_1") (pintype "passive"))
      (node (ref "U1") (pin "25") (pinfunction "(SCL_/_INT0)_PD0_25") (pintype "bidirectional"))
    )
    (net (code "73") (name "Net-(U1-(SDA_{slash}_INT1)_PD1)") (class "Default")
      (node (ref "R51") (pin "1") (pinfunction "1_1") (pintype "passive"))
      (node (ref "U1") (pin "26") (pinfunction "(SDA_/_INT1)_PD1_26") (pintype "bidirectional"))
    )
    (net (code "74") (name "Net-(U1-(T0)_PD7)") (class "Default")
      (node (ref "R54") (pin "1") (pinfunction "1_1") (pintype "passive"))
      (node (ref "U1") (pin "32") (pinfunction "(T0)_PD7_32") (pintype "bidirectional"))
    )
    (net (code "75") (name "Net-(U1-(T3_{slash}_INT6)_PE6)") (class "Default")
      (node (ref "R15") (pin "2") (pinfunction "2_2") (pintype "passive"))
      (node (ref "U1") (pin "8") (pinfunction "(T3_/_INT6)_PE6_8") (pintype "bidirectional"))
    )
    (net (code "76") (name "Net-(U1-(TOSC1_)_PG4)") (class "Default")
      (node (ref "R10") (pin "1") (pinfunction "1_1") (pintype "passive"))
      (node (ref "U1") (pin "19") (pinfunction "(TOSC1_)_PG4_19") (pintype "bidirectional"))
    )
    (net (code "77") (name "Net-(U1-(TOSC2_)_PG3)") (class "Default")
      (node (ref "R7") (pin "1") (pinfunction "1_1") (pintype "passive"))
      (node (ref "U1") (pin "18") (pinfunction "(TOSC2_)_PG3_18") (pintype "bidirectional"))
    )
    (net (code "78") (name "Net-(U1-(TXD0_{slash}_PDO)_PE1)") (class "Default")
      (node (ref "R8") (pin "2") (pinfunction "2_2") (pintype "passive"))
      (node (ref "U1") (pin "3") (pinfunction "(TXD0_/_PDO)_PE1_3") (pintype "bidirectional"))
    )
    (net (code "79") (name "Net-(U1-(TXD1_{slash}_INT3)_PD3)") (class "Default")
      (node (ref "R53") (pin "1") (pinfunction "1_1") (pintype "passive"))
      (node (ref "U1") (pin "28") (pinfunction "(TXD1_/_INT3)_PD3_28") (pintype "bidirectional"))
    )
    (net (code "80") (name "Net-(U1-(XCK0_{slash}_AIN0)_PE2)") (class "Default")
      (node (ref "R6") (pin "1") (pinfunction "1_1") (pintype "passive"))
      (node (ref "U1") (pin "4") (pinfunction "(XCK0_/_AIN0)_PE2_4") (pintype "bidirectional"))
    )
    (net (code "81") (name "Net-(U1-PA0_(AD0))") (class "Default")
      (node (ref "R45") (pin "1") (pinfunction "1_1") (pintype "passive"))
      (node (ref "U1") (pin "51") (pinfunction "PA0_(AD0)_51") (pintype "bidirectional"))
    )
    (net (code "82") (name "Net-(U1-PA1_(AD1))") (class "Default")
      (node (ref "R18") (pin "2") (pinfunction "2_2") (pintype "passive"))
      (node (ref "U1") (pin "50") (pinfunction "PA1_(AD1)_50") (pintype "bidirectional"))
    )
    (net (code "83") (name "Net-(U1-PA2_(AD2))") (class "Default")
      (node (ref "R24") (pin "1") (pinfunction "1_1") (pintype "passive"))
      (node (ref "U1") (pin "49") (pinfunction "PA2_(AD2)_49") (pintype "bidirectional"))
    )
    (net (code "84") (name "Net-(U1-PA4_(AD4))") (class "Default")
      (node (ref "R11") (pin "1") (pinfunction "1_1") (pintype "passive"))
      (node (ref "U1") (pin "47") (pinfunction "PA4_(AD4)_47") (pintype "bidirectional"))
    )
    (net (code "85") (name "Net-(U1-PA5_(AD5))") (class "Default")
      (node (ref "R14") (pin "1") (pinfunction "1_1") (pintype "passive"))
      (node (ref "U1") (pin "46") (pinfunction "PA5_(AD5)_46") (pintype "bidirectional"))
    )
    (net (code "86") (name "Net-(U1-PA6_(AD6))") (class "Default")
      (node (ref "R13") (pin "1") (pinfunction "1_1") (pintype "passive"))
      (node (ref "U1") (pin "45") (pinfunction "PA6_(AD6)_45") (pintype "bidirectional"))
    )
    (net (code "87") (name "Net-(U1-PA7_(AD7))") (class "Default")
      (node (ref "R16") (pin "1") (pinfunction "1_1") (pintype "passive"))
      (node (ref "U1") (pin "44") (pinfunction "PA7_(AD7)_44") (pintype "bidirectional"))
    )
    (net (code "88") (name "Net-(U1-PC0_(A8))") (class "Default")
      (node (ref "R19") (pin "2") (pinfunction "2_2") (pintype "passive"))
      (node (ref "U1") (pin "35") (pinfunction "PC0_(A8)_35") (pintype "bidirectional"))
    )
    (net (code "89") (name "Net-(U1-PC1_(A9))") (class "Default")
      (node (ref "R21") (pin "2") (pinfunction "2_2") (pintype "passive"))
      (node (ref "U1") (pin "36") (pinfunction "PC1_(A9)_36") (pintype "bidirectional"))
    )
    (net (code "90") (name "Net-(U1-PC2_(A10))") (class "Default")
      (node (ref "R27") (pin "1") (pinfunction "1_1") (pintype "passive"))
      (node (ref "U1") (pin "37") (pinfunction "PC2_(A10)_37") (pintype "bidirectional"))
    )
    (net (code "91") (name "Net-(U1-PC3_(A11))") (class "Default")
      (node (ref "R25") (pin "1") (pinfunction "1_1") (pintype "passive"))
      (node (ref "U1") (pin "38") (pinfunction "PC3_(A11)_38") (pintype "bidirectional"))
    )
    (net (code "92") (name "Net-(U1-PC4_(A12))") (class "Default")
      (node (ref "R46") (pin "2") (pinfunction "2_2") (pintype "passive"))
      (node (ref "U1") (pin "39") (pinfunction "PC4_(A12)_39") (pintype "bidirectional"))
    )
    (net (code "93") (name "Net-(U1-PC5_(A13))") (class "Default")
      (node (ref "R48") (pin "2") (pinfunction "2_2") (pintype "passive"))
      (node (ref "U1") (pin "40") (pinfunction "PC5_(A13)_40") (pintype "bidirectional"))
    )
    (net (code "94") (name "Net-(U1-PC6_(A14))") (class "Default")
      (node (ref "R50") (pin "2") (pinfunction "2_2") (pintype "passive"))
      (node (ref "U1") (pin "41") (pinfunction "PC6_(A14)_41") (pintype "bidirectional"))
    )
    (net (code "95") (name "Net-(U1-PC7_(A15_{slash}_CLKO))") (class "Default")
      (node (ref "R52") (pin "2") (pinfunction "2_2") (pintype "passive"))
      (node (ref "U1") (pin "42") (pinfunction "PC7_(A15_/_CLKO)_42") (pintype "bidirectional"))
    )
    (net (code "96") (name "Net-(U1-PG0_(~{WR)})") (class "Default")
      (node (ref "R1") (pin "2") (pinfunction "2_2") (pintype "passive"))
      (node (ref "U1") (pin "33") (pinfunction "PG0_(~{WR)}_33") (pintype "bidirectional"))
    )
    (net (code "97") (name "Net-(U1-PG1_(~{RD)})") (class "Default")
      (node (ref "R2") (pin "2") (pinfunction "2_2") (pintype "passive"))
      (node (ref "U1") (pin "34") (pinfunction "PG1_(~{RD)}_34") (pintype "bidirectional"))
    )
    (net (code "98") (name "Net-(U1-PG2_(ALE))") (class "Default")
      (node (ref "R5") (pin "2") (pinfunction "2_2") (pintype "passive"))
      (node (ref "U1") (pin "43") (pinfunction "PG2_(ALE)_43") (pintype "bidirectional"))
    )
    (net (code "99") (name "Net-(U1-XTAL1)") (class "Default")
      (node (ref "C6") (pin "2") (pinfunction "2_2") (pintype "passive"))
      (node (ref "Q1") (pin "1") (pinfunction "1_1") (pintype "passive"))
      (node (ref "U1") (pin "24") (pinfunction "XTAL1_24") (pintype "input"))
    )
    (net (code "100") (name "Net-(U1-XTAL2)") (class "Default")
      (node (ref "C1") (pin "2") (pinfunction "2_2") (pintype "passive"))
      (node (ref "Q1") (pin "2") (pinfunction "2_2") (pintype "passive"))
      (node (ref "U1") (pin "23") (pinfunction "XTAL2_23") (pintype "output"))
    )
    (net (code "101") (name "Net-(U3-RS)") (class "Default")
      (node (ref "CCTRL1") (pin "2") (pinfunction "2_2") (pintype "passive"))
      (node (ref "R40") (pin "2") (pinfunction "2_2") (pintype "passive"))
      (node (ref "U3") (pin "8") (pinfunction "RS_8") (pintype "input"))
    )
    (net (code "102") (name "Net-(U3-VREF)") (class "Default")
      (node (ref "R35") (pin "1") (pinfunction "1_1") (pintype "passive"))
      (node (ref "U3") (pin "5") (pinfunction "VREF_5") (pintype "output"))
    )
    (net (code "103") (name "unconnected-(Display1-Pad3)") (class "Default")
      (node (ref "Display1") (pin "3") (pinfunction "3_3") (pintype "bidirectional+no_connect"))
    )
    (net (code "104") (name "unconnected-(Display1-Pad15)") (class "Default")
      (node (ref "Display1") (pin "15") (pinfunction "15_15") (pintype "bidirectional+no_connect"))
    )
    (net (code "105") (name "unconnected-(Display1-Pad16)") (class "Default")
      (node (ref "Display1") (pin "16") (pinfunction "16_16") (pintype "bidirectional+no_connect"))
    )
    (net (code "106") (name "unconnected-(JTAG1-Pad8)") (class "Default")
      (node (ref "JTAG1") (pin "8") (pinfunction "8_8") (pintype "passive+no_connect"))
    )
    (net (code "107") (name "unconnected-(U1-(OC0A_{slash}_OC1C)_PB7-Pad17)") (class "Default")
      (node (ref "U1") (pin "17") (pinfunction "(OC0A_/_OC1C)_PB7_17") (pintype "bidirectional+no_connect"))
    )
    (net (code "108") (name "unconnected-(U1-AREF-Pad62)") (class "Default")
      (node (ref "U1") (pin "62") (pinfunction "AREF_62") (pintype "input+no_connect"))
    )
    (net (code "109") (name "unconnected-(U1-NC-Pad1)") (class "Default")
      (node (ref "U1") (pin "1") (pinfunction "NC_1") (pintype "passive+no_connect"))
    )
    (net (code "110") (name "unconnected-(U1-PA3_(AD3)-Pad48)") (class "Default")
      (node (ref "U1") (pin "48") (pinfunction "PA3_(AD3)_48") (pintype "bidirectional+no_connect"))
    )
    (net (code "111") (name "unconnected-(U1-PF0_(ADC0)-Pad61)") (class "Default")
      (node (ref "U1") (pin "61") (pinfunction "PF0_(ADC0)_61") (pintype "bidirectional+no_connect"))
    )
  )
)
